# turbo_B.net
KiCad netlist of a schematic drawn in EAGLE
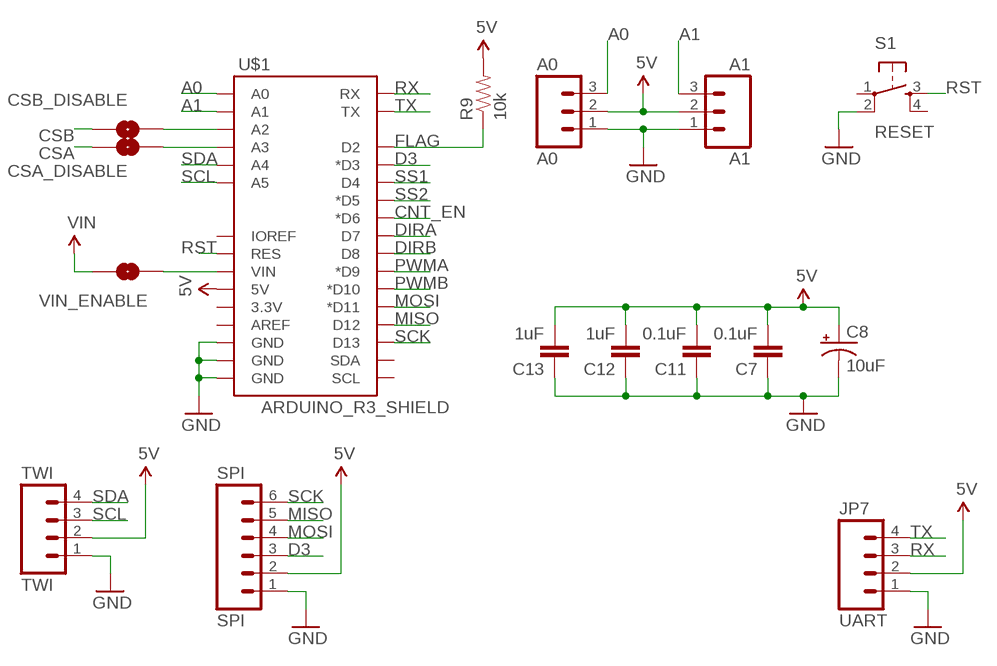
[diagram p0: schematic, sheet 1]
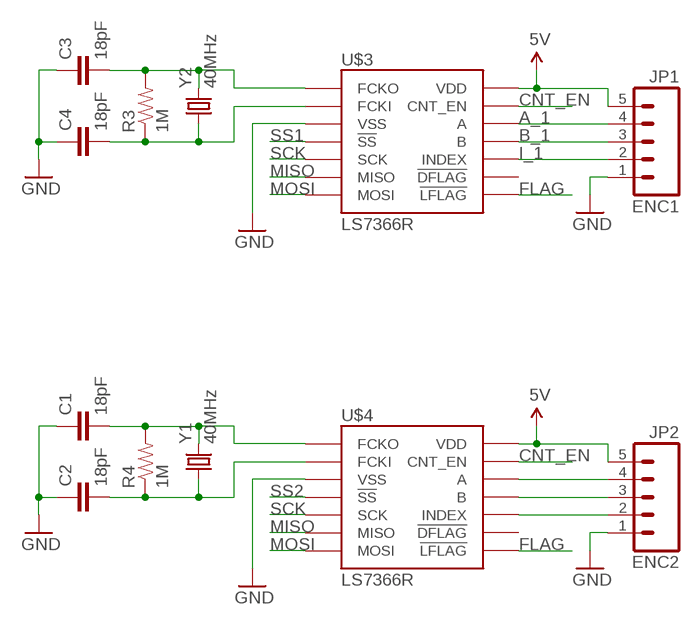
[diagram p1: schematic, sheet 2]
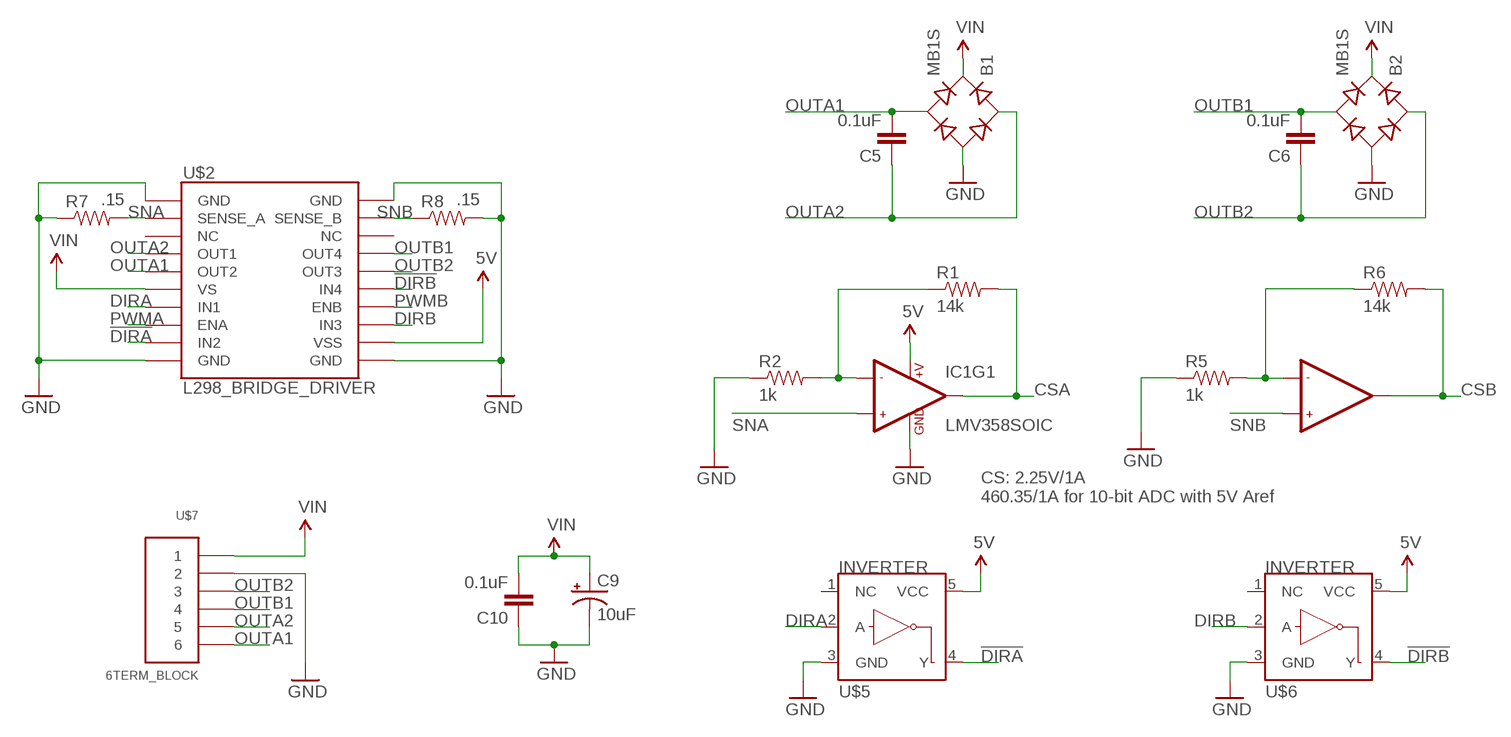
[diagram p2: schematic, sheet 3]

(export (version "E")
  (design (tool "Eeschema 10.0.6"))
  (components
    (comp (ref "A0")
      (value "A0")
      (footprint "eagle-import:1X03_LOCK")
      (libsource (lib "eagle-import") (part "M03LOCK"))
    )
    (comp (ref "A1")
      (value "A1")
      (footprint "eagle-import:1X03_LOCK")
      (libsource (lib "eagle-import") (part "M03LOCK"))
    )
    (comp (ref "C7")
      (value "0.1uF")
      (footprint "eagle-import:0603-CAP")
      (libsource (lib "eagle-import") (part "CAP0603-CAP"))
    )
    (comp (ref "C8")
      (value "10uF")
      (footprint "eagle-import:PANASONIC_C")
      (libsource (lib "eagle-import") (part "CAP_POLC"))
    )
    (comp (ref "C11")
      (value "0.1uF")
      (footprint "eagle-import:0603-CAP")
      (libsource (lib "eagle-import") (part "CAP0603-CAP"))
    )
    (comp (ref "C12")
      (value "1uF")
      (footprint "eagle-import:0603-CAP")
      (libsource (lib "eagle-import") (part "CAP0603-CAP"))
    )
    (comp (ref "C13")
      (value "1uF")
      (footprint "eagle-import:0603-CAP")
      (libsource (lib "eagle-import") (part "CAP0603-CAP"))
    )
    (comp (ref "CSA_DISABLE")
      (value "SOLDERJUMPERTRACE")
      (footprint "eagle-import:SJ_2S-TRACE")
      (libsource (lib "eagle-import") (part "SOLDERJUMPERTRACE"))
    )
    (comp (ref "CSB_DISABLE")
      (value "SOLDERJUMPERTRACE")
      (footprint "eagle-import:SJ_2S-TRACE")
      (libsource (lib "eagle-import") (part "SOLDERJUMPERTRACE"))
    )
    (comp (ref "JP7")
      (value "UART")
      (footprint "eagle-import:1X04_LOCK")
      (libsource (lib "eagle-import") (part "M04LOCK"))
    )
    (comp (ref "R9")
      (value "10k")
      (footprint "eagle-import:0603-RES")
      (libsource (lib "eagle-import") (part "RESISTOR0603-RES"))
    )
    (comp (ref "S1")
      (value "RESET")
      (footprint "eagle-import:TACTILE_SWITCH_SMD")
      (libsource (lib "eagle-import") (part "TAC_SWITCHSMD"))
    )
    (comp (ref "SPI")
      (value "SPI")
      (footprint "eagle-import:1X06_LOCK")
      (libsource (lib "eagle-import") (part "M06LOCK"))
    )
    (comp (ref "TWI")
      (value "TWI")
      (footprint "eagle-import:1X04_LOCK")
      (libsource (lib "eagle-import") (part "M04LOCK"))
    )
    (comp (ref "U$1")
      (value "ARDUINO_R3_SHIELD")
      (footprint "eagle-import:UNO_R3_SHIELD")
      (libsource (lib "eagle-import") (part "ARDUINO_R3_SHIELD"))
    )
    (comp (ref "VIN_ENABLE")
      (value "SOLDERJUMPERNO")
      (footprint "eagle-import:SJ_2S-NO")
      (libsource (lib "eagle-import") (part "SOLDERJUMPERNO"))
    )
    (comp (ref "C1")
      (value "18pF")
      (footprint "eagle-import:0603-CAP")
      (libsource (lib "eagle-import") (part "CAP0603-CAP"))
    )
    (comp (ref "C2")
      (value "18pF")
      (footprint "eagle-import:0603-CAP")
      (libsource (lib "eagle-import") (part "CAP0603-CAP"))
    )
    (comp (ref "C3")
      (value "18pF")
      (footprint "eagle-import:0603-CAP")
      (libsource (lib "eagle-import") (part "CAP0603-CAP"))
    )
    (comp (ref "C4")
      (value "18pF")
      (footprint "eagle-import:0603-CAP")
      (libsource (lib "eagle-import") (part "CAP0603-CAP"))
    )
    (comp (ref "JP1")
      (value "ENC1")
      (footprint "eagle-import:1X05_LOCK")
      (libsource (lib "eagle-import") (part "M05LOCK"))
    )
    (comp (ref "JP2")
      (value "ENC2")
      (footprint "eagle-import:1X05_LOCK")
      (libsource (lib "eagle-import") (part "M05LOCK"))
    )
    (comp (ref "R3")
      (value "1M")
      (footprint "eagle-import:0603-RES")
      (libsource (lib "eagle-import") (part "RESISTOR0603-RES"))
    )
    (comp (ref "R4")
      (value "1M")
      (footprint "eagle-import:0603-RES")
      (libsource (lib "eagle-import") (part "RESISTOR0603-RES"))
    )
    (comp (ref "U$3")
      (value "LS7366R")
      (footprint "eagle-import:SOIC14")
      (libsource (lib "eagle-import") (part "LS7366R"))
    )
    (comp (ref "U$4")
      (value "LS7366R")
      (footprint "eagle-import:SOIC14")
      (libsource (lib "eagle-import") (part "LS7366R"))
    )
    (comp (ref "Y1")
      (value "40MHz")
      (footprint "eagle-import:CRYSTAL-SMD-5X3")
      (libsource (lib "eagle-import") (part "CRYSTAL5X3"))
    )
    (comp (ref "Y2")
      (value "40MHz")
      (footprint "eagle-import:CRYSTAL-SMD-5X3")
      (libsource (lib "eagle-import") (part "CRYSTAL5X3"))
    )
    (comp (ref "B1")
      (value "MB1S")
      (footprint "eagle-import:SOIC-4")
      (libsource (lib "eagle-import") (part "MBS1"))
    )
    (comp (ref "B2")
      (value "MB1S")
      (footprint "eagle-import:SOIC-4")
      (libsource (lib "eagle-import") (part "MBS1"))
    )
    (comp (ref "C5")
      (value "0.1uF")
      (footprint "eagle-import:0603-CAP")
      (libsource (lib "eagle-import") (part "CAP0603-CAP"))
    )
    (comp (ref "C6")
      (value "0.1uF")
      (footprint "eagle-import:0603-CAP")
      (libsource (lib "eagle-import") (part "CAP0603-CAP"))
    )
    (comp (ref "C9")
      (value "10uF")
      (footprint "eagle-import:PANASONIC_C")
      (libsource (lib "eagle-import") (part "CAP_POLC"))
    )
    (comp (ref "C10")
      (value "0.1uF")
      (footprint "eagle-import:0603-CAP")
      (libsource (lib "eagle-import") (part "CAP0603-CAP"))
    )
    (comp (ref "IC1")
      (value "LMV358SOIC")
      (footprint "eagle-import:SO08")
      (libsource (lib "eagle-import") (part "LMV358SOIC"))
    )
    (comp (ref "R1")
      (value "14k")
      (footprint "eagle-import:0603-RES")
      (libsource (lib "eagle-import") (part "RESISTOR0603-RES"))
    )
    (comp (ref "R2")
      (value "1k")
      (footprint "eagle-import:0603-RES")
      (libsource (lib "eagle-import") (part "RESISTOR0603-RES"))
    )
    (comp (ref "R5")
      (value "1k")
      (footprint "eagle-import:0603-RES")
      (libsource (lib "eagle-import") (part "RESISTOR0603-RES"))
    )
    (comp (ref "R6")
      (value "14k")
      (footprint "eagle-import:0603-RES")
      (libsource (lib "eagle-import") (part "RESISTOR0603-RES"))
    )
    (comp (ref "R7")
      (value ".15")
      (footprint "eagle-import:1206")
      (libsource (lib "eagle-import") (part "SparkFun-Resistors_RESISTOR1206"))
    )
    (comp (ref "R8")
      (value ".15")
      (footprint "eagle-import:1206")
      (libsource (lib "eagle-import") (part "SparkFun-Resistors_RESISTOR1206"))
    )
    (comp (ref "U$2")
      (value "L298_BRIDGE_DRIVER")
      (footprint "eagle-import:POWERSO20")
      (libsource (lib "eagle-import") (part "L298_BRIDGE_DRIVER"))
    )
    (comp (ref "U$5")
      (value "INVERTER")
      (footprint "eagle-import:SOT23-5")
      (libsource (lib "eagle-import") (part "INVERTER"))
    )
    (comp (ref "U$6")
      (value "INVERTER")
      (footprint "eagle-import:SOT23-5")
      (libsource (lib "eagle-import") (part "INVERTER"))
    )
    (comp (ref "U$7")
      (value "6TERM_BLOCK")
      (footprint "eagle-import:6TERM_BLOCK")
      (libsource (lib "eagle-import") (part "6TERM_BLOCK"))
    )
  )
  (nets
    (net (code "1") (name "5V") (class "Default")
      (node (ref "A0") (pin "2") (pinfunction "2_2") (pintype "passive"))
      (node (ref "A1") (pin "2") (pinfunction "2_2") (pintype "passive"))
      (node (ref "C11") (pin "2") (pinfunction "2_2") (pintype "passive"))
      (node (ref "C12") (pin "2") (pinfunction "2_2") (pintype "passive"))
      (node (ref "C13") (pin "2") (pinfunction "2_2") (pintype "passive"))
      (node (ref "C7") (pin "2") (pinfunction "2_2") (pintype "passive"))
      (node (ref "C8") (pin "+") (pinfunction "+_+") (pintype "passive"))
      (node (ref "IC1") (pin "8") (pinfunction "+V_8") (pintype "power_in"))
      (node (ref "JP1") (pin "5") (pinfunction "5_5") (pintype "passive"))
      (node (ref "JP2") (pin "5") (pinfunction "5_5") (pintype "passive"))
      (node (ref "JP7") (pin "2") (pinfunction "2_2") (pintype "passive"))
      (node (ref "R9") (pin "2") (pinfunction "2_2") (pintype "passive"))
      (node (ref "SPI") (pin "2") (pinfunction "2_2") (pintype "passive"))
      (node (ref "TWI") (pin "2") (pinfunction "2_2") (pintype "passive"))
      (node (ref "U$1") (pin "5V") (pinfunction "5V_5V") (pintype "bidirectional"))
      (node (ref "U$2") (pin "12") (pinfunction "VSS_12") (pintype "bidirectional"))
      (node (ref "U$3") (pin "14") (pinfunction "VDD_14") (pintype "bidirectional"))
      (node (ref "U$4") (pin "14") (pinfunction "VDD_14") (pintype "bidirectional"))
      (node (ref "U$5") (pin "5") (pinfunction "VCC_5") (pintype "bidirectional"))
      (node (ref "U$6") (pin "5") (pinfunction "VCC_5") (pintype "bidirectional"))
    )
    (net (code "2") (name "A0") (class "Default")
      (node (ref "A0") (pin "3") (pinfunction "3_3") (pintype "passive"))
      (node (ref "U$1") (pin "A0") (pinfunction "A0_A0") (pintype "bidirectional"))
    )
    (net (code "3") (name "A1") (class "Default")
      (node (ref "A1") (pin "3") (pinfunction "3_3") (pintype "passive"))
      (node (ref "U$1") (pin "A1") (pinfunction "A1_A1") (pintype "bidirectional"))
    )
    (net (code "4") (name "A_1") (class "Default")
      (node (ref "JP1") (pin "4") (pinfunction "4_4") (pintype "passive"))
      (node (ref "U$3") (pin "12") (pinfunction "A_12") (pintype "bidirectional"))
    )
    (net (code "5") (name "B_1") (class "Default")
      (node (ref "JP1") (pin "3") (pinfunction "3_3") (pintype "passive"))
      (node (ref "U$3") (pin "11") (pinfunction "B_11") (pintype "bidirectional"))
    )
    (net (code "6") (name "CNT_EN") (class "Default")
      (node (ref "U$1") (pin "D6") (pinfunction "*D6_D6") (pintype "bidirectional"))
      (node (ref "U$3") (pin "13") (pinfunction "CNT_EN_13") (pintype "bidirectional"))
      (node (ref "U$4") (pin "13") (pinfunction "CNT_EN_13") (pintype "bidirectional"))
    )
    (net (code "7") (name "CSA") (class "Default")
      (node (ref "CSA_DISABLE") (pin "2") (pinfunction "2_2") (pintype "passive"))
      (node (ref "IC1") (pin "1") (pinfunction "OUT1_1") (pintype "output"))
      (node (ref "R1") (pin "2") (pinfunction "2_2") (pintype "passive"))
    )
    (net (code "8") (name "CSB") (class "Default")
      (node (ref "CSB_DISABLE") (pin "2") (pinfunction "2_2") (pintype "passive"))
      (node (ref "IC1") (pin "7") (pinfunction "OUT2_7") (pintype "output"))
      (node (ref "R6") (pin "2") (pinfunction "2_2") (pintype "passive"))
    )
    (net (code "9") (name "D3") (class "Default")
      (node (ref "SPI") (pin "3") (pinfunction "3_3") (pintype "passive"))
      (node (ref "U$1") (pin "D3") (pinfunction "*D3_D3") (pintype "bidirectional"))
    )
    (net (code "10") (name "DIRA") (class "Default")
      (node (ref "U$1") (pin "D7") (pinfunction "D7_D7") (pintype "bidirectional"))
      (node (ref "U$2") (pin "7") (pinfunction "IN1_7") (pintype "bidirectional"))
      (node (ref "U$5") (pin "2") (pinfunction "A_2") (pintype "bidirectional"))
    )
    (net (code "11") (name "DIRB") (class "Default")
      (node (ref "U$1") (pin "D8") (pinfunction "D8_D8") (pintype "bidirectional"))
      (node (ref "U$2") (pin "13") (pinfunction "IN3_13") (pintype "bidirectional"))
      (node (ref "U$6") (pin "2") (pinfunction "A_2") (pintype "bidirectional"))
    )
    (net (code "12") (name "FLAG") (class "Default")
      (node (ref "R9") (pin "1") (pinfunction "1_1") (pintype "passive"))
      (node (ref "U$1") (pin "D2") (pinfunction "D2_D2") (pintype "bidirectional"))
      (node (ref "U$3") (pin "8") (pinfunction "~{LFLAG}_8") (pintype "bidirectional"))
      (node (ref "U$4") (pin "8") (pinfunction "~{LFLAG}_8") (pintype "bidirectional"))
    )
    (net (code "13") (name "GND") (class "Default")
      (node (ref "A0") (pin "1") (pinfunction "1_1") (pintype "passive"))
      (node (ref "A1") (pin "1") (pinfunction "1_1") (pintype "passive"))
      (node (ref "B1") (pin "-") (pinfunction "-_-") (pintype "passive"))
      (node (ref "B2") (pin "-") (pinfunction "-_-") (pintype "passive"))
      (node (ref "C1") (pin "1") (pinfunction "1_1") (pintype "passive"))
      (node (ref "C10") (pin "1") (pinfunction "1_1") (pintype "passive"))
      (node (ref "C11") (pin "1") (pinfunction "1_1") (pintype "passive"))
      (node (ref "C12") (pin "1") (pinfunction "1_1") (pintype "passive"))
      (node (ref "C13") (pin "1") (pinfunction "1_1") (pintype "passive"))
      (node (ref "C2") (pin "1") (pinfunction "1_1") (pintype "passive"))
      (node (ref "C3") (pin "1") (pinfunction "1_1") (pintype "passive"))
      (node (ref "C4") (pin "1") (pinfunction "1_1") (pintype "passive"))
      (node (ref "C7") (pin "1") (pinfunction "1_1") (pintype "passive"))
      (node (ref "C8") (pin "-") (pinfunction "-_-") (pintype "passive"))
      (node (ref "C9") (pin "-") (pinfunction "-_-") (pintype "passive"))
      (node (ref "IC1") (pin "4") (pinfunction "GND_4") (pintype "power_in"))
      (node (ref "JP1") (pin "1") (pinfunction "1_1") (pintype "passive"))
      (node (ref "JP2") (pin "1") (pinfunction "1_1") (pintype "passive"))
      (node (ref "JP7") (pin "1") (pinfunction "1_1") (pintype "passive"))
      (node (ref "R2") (pin "1") (pinfunction "1_1") (pintype "passive"))
      (node (ref "R5") (pin "1") (pinfunction "1_1") (pintype "passive"))
      (node (ref "R7") (pin "1") (pinfunction "1_1") (pintype "passive"))
      (node (ref "R8") (pin "2") (pinfunction "2_2") (pintype "passive"))
      (node (ref "S1") (pin "2") (pinfunction "2_2") (pintype "passive"))
      (node (ref "SPI") (pin "1") (pinfunction "1_1") (pintype "passive"))
      (node (ref "TWI") (pin "1") (pinfunction "1_1") (pintype "passive"))
      (node (ref "U$1") (pin "GND@0") (pinfunction "GND_GND@0") (pintype "bidirectional"))
      (node (ref "U$1") (pin "GND@1") (pinfunction "GND_GND@1") (pintype "bidirectional"))
      (node (ref "U$1") (pin "GND@2") (pinfunction "GND_GND@2") (pintype "bidirectional"))
      (node (ref "U$2") (pin "1") (pinfunction "GND_1") (pintype "bidirectional"))
      (node (ref "U$2") (pin "10") (pinfunction "GND_10") (pintype "bidirectional"))
      (node (ref "U$2") (pin "11") (pinfunction "GND_11") (pintype "bidirectional"))
      (node (ref "U$2") (pin "20") (pinfunction "GND_20") (pintype "bidirectional"))
      (node (ref "U$2") (pin "P$1") (pinfunction "GND_P$1") (pintype "bidirectional"))
      (node (ref "U$3") (pin "3") (pinfunction "VSS_3") (pintype "bidirectional"))
      (node (ref "U$4") (pin "3") (pinfunction "VSS_3") (pintype "bidirectional"))
      (node (ref "U$5") (pin "3") (pinfunction "GND_3") (pintype "bidirectional"))
      (node (ref "U$6") (pin "3") (pinfunction "GND_3") (pintype "bidirectional"))
      (node (ref "U$7") (pin "P$2") (pinfunction "2_P$2") (pintype "bidirectional"))
    )
    (net (code "14") (name "I_1") (class "Default")
      (node (ref "JP1") (pin "2") (pinfunction "2_2") (pintype "passive"))
      (node (ref "U$3") (pin "10") (pinfunction "INDEX_10") (pintype "bidirectional"))
    )
    (net (code "15") (name "MISO") (class "Default")
      (node (ref "SPI") (pin "5") (pinfunction "5_5") (pintype "passive"))
      (node (ref "U$1") (pin "D12") (pinfunction "D12_D12") (pintype "bidirectional"))
      (node (ref "U$3") (pin "6") (pinfunction "MISO_6") (pintype "bidirectional"))
      (node (ref "U$4") (pin "6") (pinfunction "MISO_6") (pintype "bidirectional"))
    )
    (net (code "16") (name "MOSI") (class "Default")
      (node (ref "SPI") (pin "4") (pinfunction "4_4") (pintype "passive"))
      (node (ref "U$1") (pin "D11") (pinfunction "*D11_D11") (pintype "bidirectional"))
      (node (ref "U$3") (pin "7") (pinfunction "MOSI_7") (pintype "bidirectional"))
      (node (ref "U$4") (pin "7") (pinfunction "MOSI_7") (pintype "bidirectional"))
    )
    (net (code "17") (name "Net-(CSA_DISABLE-Pad1)") (class "Default")
      (node (ref "CSA_DISABLE") (pin "1") (pinfunction "1_1") (pintype "passive"))
      (node (ref "U$1") (pin "A3") (pinfunction "A3_A3") (pintype "bidirectional"))
    )
    (net (code "18") (name "Net-(CSB_DISABLE-Pad1)") (class "Default")
      (node (ref "CSB_DISABLE") (pin "1") (pinfunction "1_1") (pintype "passive"))
      (node (ref "U$1") (pin "A2") (pinfunction "A2_A2") (pintype "bidirectional"))
    )
    (net (code "19") (name "Net-(IC1A--IN1)") (class "Default")
      (node (ref "IC1") (pin "2") (pinfunction "-IN1_2") (pintype "input"))
      (node (ref "R1") (pin "1") (pinfunction "1_1") (pintype "passive"))
      (node (ref "R2") (pin "2") (pinfunction "2_2") (pintype "passive"))
    )
    (net (code "20") (name "Net-(IC1B--IN2)") (class "Default")
      (node (ref "IC1") (pin "6") (pinfunction "-IN2_6") (pintype "input"))
      (node (ref "R5") (pin "2") (pinfunction "2_2") (pintype "passive"))
      (node (ref "R6") (pin "1") (pinfunction "1_1") (pintype "passive"))
    )
    (net (code "21") (name "Net-(U$1-PadVIN)") (class "Default")
      (node (ref "U$1") (pin "VIN") (pinfunction "VIN_VIN") (pintype "bidirectional"))
      (node (ref "VIN_ENABLE") (pin "2") (pinfunction "2_2") (pintype "passive"))
    )
    (net (code "22") (name "Net-(U$3-FCKI)") (class "Default")
      (node (ref "C4") (pin "2") (pinfunction "2_2") (pintype "passive"))
      (node (ref "R3") (pin "1") (pinfunction "1_1") (pintype "passive"))
      (node (ref "U$3") (pin "2") (pinfunction "FCKI_2") (pintype "bidirectional"))
      (node (ref "Y2") (pin "1") (pinfunction "1_1") (pintype "passive"))
    )
    (net (code "23") (name "Net-(U$3-FCKO)") (class "Default")
      (node (ref "C3") (pin "2") (pinfunction "2_2") (pintype "passive"))
      (node (ref "R3") (pin "2") (pinfunction "2_2") (pintype "passive"))
      (node (ref "U$3") (pin "1") (pinfunction "FCKO_1") (pintype "bidirectional"))
      (node (ref "Y2") (pin "3") (pinfunction "2_3") (pintype "passive"))
    )
    (net (code "24") (name "Net-(U$4-A)") (class "Default")
      (node (ref "JP2") (pin "4") (pinfunction "4_4") (pintype "passive"))
      (node (ref "U$4") (pin "12") (pinfunction "A_12") (pintype "bidirectional"))
    )
    (net (code "25") (name "Net-(U$4-B)") (class "Default")
      (node (ref "JP2") (pin "3") (pinfunction "3_3") (pintype "passive"))
      (node (ref "U$4") (pin "11") (pinfunction "B_11") (pintype "bidirectional"))
    )
    (net (code "26") (name "Net-(U$4-FCKI)") (class "Default")
      (node (ref "C2") (pin "2") (pinfunction "2_2") (pintype "passive"))
      (node (ref "R4") (pin "1") (pinfunction "1_1") (pintype "passive"))
      (node (ref "U$4") (pin "2") (pinfunction "FCKI_2") (pintype "bidirectional"))
      (node (ref "Y1") (pin "1") (pinfunction "1_1") (pintype "passive"))
    )
    (net (code "27") (name "Net-(U$4-FCKO)") (class "Default")
      (node (ref "C1") (pin "2") (pinfunction "2_2") (pintype "passive"))
      (node (ref "R4") (pin "2") (pinfunction "2_2") (pintype "passive"))
      (node (ref "U$4") (pin "1") (pinfunction "FCKO_1") (pintype "bidirectional"))
      (node (ref "Y1") (pin "3") (pinfunction "2_3") (pintype "passive"))
    )
    (net (code "28") (name "Net-(U$4-INDEX)") (class "Default")
      (node (ref "JP2") (pin "2") (pinfunction "2_2") (pintype "passive"))
      (node (ref "U$4") (pin "10") (pinfunction "INDEX_10") (pintype "bidirectional"))
    )
    (net (code "29") (name "OUTA1") (class "Default")
      (node (ref "B1") (pin "~2") (pinfunction "AC2_~2") (pintype "passive"))
      (node (ref "C5") (pin "2") (pinfunction "2_2") (pintype "passive"))
      (node (ref "U$2") (pin "5") (pinfunction "OUT2_5") (pintype "bidirectional"))
      (node (ref "U$7") (pin "P$6") (pinfunction "6_P$6") (pintype "bidirectional"))
    )
    (net (code "30") (name "OUTA2") (class "Default")
      (node (ref "B1") (pin "~1") (pinfunction "AC1_~1") (pintype "passive"))
      (node (ref "C5") (pin "1") (pinfunction "1_1") (pintype "passive"))
      (node (ref "U$2") (pin "4") (pinfunction "OUT1_4") (pintype "bidirectional"))
      (node (ref "U$7") (pin "P$5") (pinfunction "5_P$5") (pintype "bidirectional"))
    )
    (net (code "31") (name "OUTB1") (class "Default")
      (node (ref "B2") (pin "~2") (pinfunction "AC2_~2") (pintype "passive"))
      (node (ref "C6") (pin "2") (pinfunction "2_2") (pintype "passive"))
      (node (ref "U$2") (pin "17") (pinfunction "OUT4_17") (pintype "bidirectional"))
      (node (ref "U$7") (pin "P$4") (pinfunction "4_P$4") (pintype "bidirectional"))
    )
    (net (code "32") (name "OUTB2") (class "Default")
      (node (ref "B2") (pin "~1") (pinfunction "AC1_~1") (pintype "passive"))
      (node (ref "C6") (pin "1") (pinfunction "1_1") (pintype "passive"))
      (node (ref "U$2") (pin "16") (pinfunction "OUT3_16") (pintype "bidirectional"))
      (node (ref "U$7") (pin "P$3") (pinfunction "3_P$3") (pintype "bidirectional"))
    )
    (net (code "33") (name "PWMA") (class "Default")
      (node (ref "U$1") (pin "D9") (pinfunction "*D9_D9") (pintype "bidirectional"))
      (node (ref "U$2") (pin "8") (pinfunction "ENA_8") (pintype "bidirectional"))
    )
    (net (code "34") (name "PWMB") (class "Default")
      (node (ref "U$1") (pin "D10") (pinfunction "*D10_D10") (pintype "bidirectional"))
      (node (ref "U$2") (pin "14") (pinfunction "ENB_14") (pintype "bidirectional"))
    )
    (net (code "35") (name "RST") (class "Default")
      (node (ref "S1") (pin "3") (pinfunction "3_3") (pintype "passive"))
      (node (ref "U$1") (pin "RES") (pinfunction "RES_RES") (pintype "bidirectional"))
    )
    (net (code "36") (name "RX") (class "Default")
      (node (ref "JP7") (pin "3") (pinfunction "3_3") (pintype "passive"))
      (node (ref "U$1") (pin "RX") (pinfunction "RX_RX") (pintype "bidirectional"))
    )
    (net (code "37") (name "SCK") (class "Default")
      (node (ref "SPI") (pin "6") (pinfunction "6_6") (pintype "passive"))
      (node (ref "U$1") (pin "D13") (pinfunction "D13_D13") (pintype "bidirectional"))
      (node (ref "U$3") (pin "5") (pinfunction "SCK_5") (pintype "bidirectional"))
      (node (ref "U$4") (pin "5") (pinfunction "SCK_5") (pintype "bidirectional"))
    )
    (net (code "38") (name "SCL") (class "Default")
      (node (ref "TWI") (pin "3") (pinfunction "3_3") (pintype "passive"))
      (node (ref "U$1") (pin "A5") (pinfunction "A5_A5") (pintype "bidirectional"))
    )
    (net (code "39") (name "SDA") (class "Default")
      (node (ref "TWI") (pin "4") (pinfunction "4_4") (pintype "passive"))
      (node (ref "U$1") (pin "A4") (pinfunction "A4_A4") (pintype "bidirectional"))
    )
    (net (code "40") (name "SNA") (class "Default")
      (node (ref "IC1") (pin "3") (pinfunction "+IN1_3") (pintype "input"))
      (node (ref "R7") (pin "2") (pinfunction "2_2") (pintype "passive"))
      (node (ref "U$2") (pin "2") (pinfunction "SENSE_A_2") (pintype "bidirectional"))
    )
    (net (code "41") (name "SNB") (class "Default")
      (node (ref "IC1") (pin "5") (pinfunction "+IN2_5") (pintype "input"))
      (node (ref "R8") (pin "1") (pinfunction "1_1") (pintype "passive"))
      (node (ref "U$2") (pin "19") (pinfunction "SENSE_B_19") (pintype "bidirectional"))
    )
    (net (code "42") (name "SS1") (class "Default")
      (node (ref "U$1") (pin "D4") (pinfunction "D4_D4") (pintype "bidirectional"))
      (node (ref "U$3") (pin "4") (pinfunction "~{SS}_4") (pintype "bidirectional"))
    )
    (net (code "43") (name "SS2") (class "Default")
      (node (ref "U$1") (pin "D5") (pinfunction "*D5_D5") (pintype "bidirectional"))
      (node (ref "U$4") (pin "4") (pinfunction "~{SS}_4") (pintype "bidirectional"))
    )
    (net (code "44") (name "TX") (class "Default")
      (node (ref "JP7") (pin "4") (pinfunction "4_4") (pintype "passive"))
      (node (ref "U$1") (pin "TX") (pinfunction "TX_TX") (pintype "bidirectional"))
    )
    (net (code "45") (name "VIN") (class "Default")
      (node (ref "B1") (pin "+") (pinfunction "+_+") (pintype "passive"))
      (node (ref "B2") (pin "+") (pinfunction "+_+") (pintype "passive"))
      (node (ref "C10") (pin "2") (pinfunction "2_2") (pintype "passive"))
      (node (ref "C9") (pin "+") (pinfunction "+_+") (pintype "passive"))
      (node (ref "U$2") (pin "6") (pinfunction "VS_6") (pintype "bidirectional"))
      (node (ref "U$7") (pin "P$1") (pinfunction "1_P$1") (pintype "bidirectional"))
      (node (ref "VIN_ENABLE") (pin "1") (pinfunction "1_1") (pintype "passive"))
    )
    (net (code "46") (name "unconnected-(S1-Pad1)") (class "Default")
      (node (ref "S1") (pin "1") (pinfunction "1_1") (pintype "passive"))
    )
    (net (code "47") (name "unconnected-(S1-Pad4)") (class "Default")
      (node (ref "S1") (pin "4") (pinfunction "4_4") (pintype "passive"))
    )
    (net (code "48") (name "unconnected-(U$1-Pad3.3V)") (class "Default")
      (node (ref "U$1") (pin "3.3V") (pinfunction "3.3V_3.3V") (pintype "bidirectional"))
    )
    (net (code "49") (name "unconnected-(U$1-PadAREF)") (class "Default")
      (node (ref "U$1") (pin "AREF") (pinfunction "AREF_AREF") (pintype "bidirectional"))
    )
    (net (code "50") (name "unconnected-(U$1-PadIOREF)") (class "Default")
      (node (ref "U$1") (pin "IOREF") (pinfunction "IOREF_IOREF") (pintype "bidirectional"))
    )
    (net (code "51") (name "unconnected-(U$1-PadSCL)") (class "Default")
      (node (ref "U$1") (pin "SCL") (pinfunction "SCL_SCL") (pintype "bidirectional"))
    )
    (net (code "52") (name "unconnected-(U$1-PadSDA)") (class "Default")
      (node (ref "U$1") (pin "SDA") (pinfunction "SDA_SDA") (pintype "bidirectional"))
    )
    (net (code "53") (name "unconnected-(U$2-NC-Pad3)") (class "Default")
      (node (ref "U$2") (pin "3") (pinfunction "NC_3") (pintype "bidirectional"))
    )
    (net (code "54") (name "unconnected-(U$2-NC-Pad18)") (class "Default")
      (node (ref "U$2") (pin "18") (pinfunction "NC_18") (pintype "bidirectional"))
    )
    (net (code "55") (name "unconnected-(U$3-~{DFLAG}-Pad9)") (class "Default")
      (node (ref "U$3") (pin "9") (pinfunction "~{DFLAG}_9") (pintype "bidirectional"))
    )
    (net (code "56") (name "unconnected-(U$4-~{DFLAG}-Pad9)") (class "Default")
      (node (ref "U$4") (pin "9") (pinfunction "~{DFLAG}_9") (pintype "bidirectional"))
    )
    (net (code "57") (name "unconnected-(U$5-NC-Pad1)") (class "Default")
      (node (ref "U$5") (pin "1") (pinfunction "NC_1") (pintype "bidirectional"))
    )
    (net (code "58") (name "unconnected-(U$6-NC-Pad1)") (class "Default")
      (node (ref "U$6") (pin "1") (pinfunction "NC_1") (pintype "bidirectional"))
    )
    (net (code "59") (name "~{DIRA}") (class "Default")
      (node (ref "U$2") (pin "9") (pinfunction "IN2_9") (pintype "bidirectional"))
      (node (ref "U$5") (pin "4") (pinfunction "Y_4") (pintype "bidirectional"))
    )
    (net (code "60") (name "~{DIRB}") (class "Default")
      (node (ref "U$2") (pin "15") (pinfunction "IN4_15") (pintype "bidirectional"))
      (node (ref "U$6") (pin "4") (pinfunction "Y_4") (pintype "bidirectional"))
    )
  )
)
